# Buckv5.net
KiCad netlist of a schematic drawn in Altium Designer
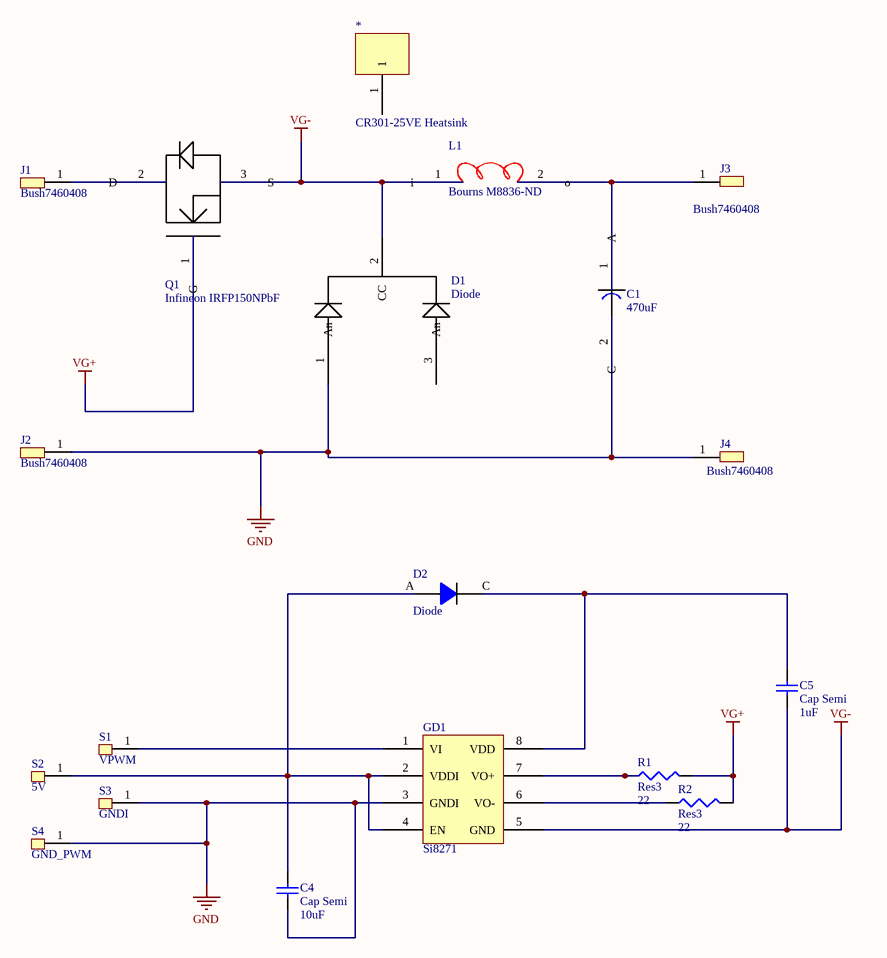
[diagram p0: Buckv5.SchDoc]

(export (version "E")
  (design (tool "Eeschema 10.0.6"))
  (components
    (comp (ref "*")
      (value "CR301-25VE Heatsink")
      (footprint "CR301-25VE")
      (description "Ohmite Heatsink   CR301-25VE Mouser 588-CR301-25VE")
      (libsource (lib "Buck_Library") (part "CR301-25VE Heatsink"))
    )
    (comp (ref "C1")
      (value "470uF")
      (footprint "EPCOS TDK B4851")
      (libsource (lib "Buck_Library") (part "470uF"))
    )
    (comp (ref "C4")
      (value "Cap Semi")
      (footprint "C1210")
      (description "CAP CER 10UF 50V X7S 1210 @Digikey 445-4537-1-ND or C3225X7S1H106M250AB")
      (fields (field (name "ALTIUM_VALUE") "10uF") (field (name "PUBLISHER") "Altium Limited"))
      (libsource (lib "Miscellaneous Devices") (part "Cap Semi"))
    )
    (comp (ref "C5")
      (value "Cap Semi")
      (footprint "C1210")
      (description "Samsung Electro-Mechanics CAP Ceramic 1uF 50V Digikey 1276-1811-1-ND")
      (fields (field (name "ALTIUM_VALUE") "1uF") (field (name "PUBLISHER") "Altium Limited"))
      (libsource (lib "Miscellaneous Devices") (part "Cap Semi"))
    )
    (comp (ref "D1")
      (value "Diode")
      (footprint "TO-247AC")
      (description "Vishay Semiconductors Schottky Rectifier Diode\r\nDigikey VS-STPS30L60CW-N3GI-ND")
      (libsource (lib "Buck_Library") (part "Vishay Semiconductors VS-STPS30L60CW-N3"))
    )
    (comp (ref "D2")
      (value "Diode")
      (footprint "SOD128Diode")
      (description "Schottky Diode 30V 5A\r\nDigikey 568-6519-1-ND")
      (libsource (lib "Buck_Library") (part "Diode"))
    )
    (comp (ref "GD1")
      (value "Si8271")
      (footprint "IPC-7351 SOIC127P600X173-8N")
      (description "8-Pin Gate Driver")
      (libsource (lib "Buck_Library") (part "Si8271"))
    )
    (comp (ref "J1")
      (value "Bush7460408")
      (footprint "Bush7460408")
      (libsource (lib "") (part "Bush7460408_1"))
    )
    (comp (ref "J2")
      (value "Bush7460408")
      (footprint "Bush7460408")
      (libsource (lib "") (part "Bush7460408_1"))
    )
    (comp (ref "J3")
      (value "Bush7460408")
      (footprint "Bush7460408")
      (libsource (lib "Buck_Library") (part "Bush7460408"))
    )
    (comp (ref "J4")
      (value "Bush7460408")
      (footprint "Bush7460408")
      (libsource (lib "Buck_Library") (part "Bush7460408"))
    )
    (comp (ref "L1")
      (value "Bourns M8836-ND")
      (footprint "Bourns M8836-ND")
      (libsource (lib "Buck_Library") (part "Bourns M8836-ND"))
    )
    (comp (ref "Q1")
      (value "Infineon IRFP150NPbF")
      (footprint "Infineon IRFP150NPbF")
      (libsource (lib "Buck_Library") (part "Infineon IRFP150NPbF"))
    )
    (comp (ref "R1")
      (value "Res3")
      (footprint "14-1210")
      (description "Stackpole Electronics Resistor 22 Ohms\r\n0.5W Digikey RMCF1210JT22R0TR-ND")
      (fields (field (name "ALTIUM_VALUE") "22") (field (name "PUBLISHER") "Altium Limited"))
      (libsource (lib "Miscellaneous Devices") (part "Res3"))
    )
    (comp (ref "R2")
      (value "Res3")
      (footprint "14-1210")
      (description "Stackpole Electronics Resistor 22 Ohms\r\n0.5W Digikey RMCF1210JT22R0TR-ND")
      (fields (field (name "ALTIUM_VALUE") "22") (field (name "PUBLISHER") "Altium Limited"))
      (libsource (lib "Miscellaneous Devices") (part "Res3"))
    )
    (comp (ref "S1")
      (value "VPWM")
      (footprint "Sensor_Connecter")
      (description "Sensor Connecter")
      (libsource (lib "Buck_Library") (part "Sensor_Connecter"))
    )
    (comp (ref "S2")
      (value "5V")
      (footprint "Sensor_Connecter")
      (description "Sensor Connecter")
      (libsource (lib "Buck_Library") (part "Sensor_Connecter"))
    )
    (comp (ref "S3")
      (value "GNDI")
      (footprint "Sensor_Connecter")
      (description "Sensor Connecter")
      (libsource (lib "Buck_Library") (part "Sensor_Connecter"))
    )
    (comp (ref "S4")
      (value "GND_PWM")
      (footprint "Sensor_Connecter")
      (description "Sensor Connecter")
      (libsource (lib "Buck_Library") (part "Sensor_Connecter"))
    )
  )
  (nets
    (net (code "1") (name "GND") (class "Default")
      (node (ref "C1") (pin "2") (pinfunction "C_2") (pintype "passive"))
      (node (ref "C4") (pin "1") (pinfunction "1_1") (pintype "passive"))
      (node (ref "D1") (pin "1") (pinfunction "An_1") (pintype "passive"))
      (node (ref "GD1") (pin "3") (pinfunction "GNDI_3") (pintype "passive"))
      (node (ref "J2") (pin "1") (pinfunction "1_1") (pintype "passive"))
      (node (ref "J4") (pin "1") (pinfunction "1_1") (pintype "passive"))
      (node (ref "S3") (pin "1") (pinfunction "1_1") (pintype "passive"))
      (node (ref "S4") (pin "1") (pinfunction "1_1") (pintype "passive"))
    )
    (net (code "2") (name "Net-(C1-A)") (class "Default")
      (node (ref "C1") (pin "1") (pinfunction "A_1") (pintype "passive"))
      (node (ref "J3") (pin "1") (pinfunction "1_1") (pintype "passive"))
      (node (ref "L1") (pin "2") (pinfunction "o_2") (pintype "passive"))
    )
    (net (code "3") (name "Net-(GD1-EN)") (class "Default")
      (node (ref "C4") (pin "2") (pinfunction "2_2") (pintype "passive"))
      (node (ref "D2") (pin "A") (pinfunction "A_A") (pintype "passive"))
      (node (ref "GD1") (pin "2") (pinfunction "VDDI_2") (pintype "passive"))
      (node (ref "GD1") (pin "4") (pinfunction "EN_4") (pintype "passive"))
      (node (ref "S2") (pin "1") (pinfunction "1_1") (pintype "passive"))
    )
    (net (code "4") (name "Net-(GD1-VDD)") (class "Default")
      (node (ref "C5") (pin "2") (pinfunction "2_2") (pintype "passive"))
      (node (ref "D2") (pin "C") (pinfunction "C_C") (pintype "passive"))
      (node (ref "GD1") (pin "8") (pinfunction "VDD_8") (pintype "passive"))
    )
    (net (code "5") (name "Net-(GD1-VI)") (class "Default")
      (node (ref "GD1") (pin "1") (pinfunction "VI_1") (pintype "passive"))
      (node (ref "S1") (pin "1") (pinfunction "1_1") (pintype "passive"))
    )
    (net (code "6") (name "Net-(GD1-VO+)") (class "Default")
      (node (ref "GD1") (pin "7") (pinfunction "VO+_7") (pintype "passive"))
      (node (ref "R1") (pin "1") (pinfunction "1_1") (pintype "passive"))
    )
    (net (code "7") (name "Net-(GD1-VO-)") (class "Default")
      (node (ref "GD1") (pin "6") (pinfunction "VO-_6") (pintype "passive"))
      (node (ref "R2") (pin "1") (pinfunction "1_1") (pintype "passive"))
    )
    (net (code "8") (name "Net-(Q1-D)") (class "Default")
      (node (ref "J1") (pin "1") (pinfunction "1_1") (pintype "passive"))
      (node (ref "Q1") (pin "2") (pinfunction "D_2") (pintype "passive"))
    )
    (net (code "9") (name "VG+") (class "Default")
      (node (ref "Q1") (pin "1") (pinfunction "G_1") (pintype "passive"))
      (node (ref "R1") (pin "2") (pinfunction "2_2") (pintype "passive"))
      (node (ref "R2") (pin "2") (pinfunction "2_2") (pintype "passive"))
    )
    (net (code "10") (name "VG-") (class "Default")
      (node (ref "C5") (pin "1") (pinfunction "1_1") (pintype "passive"))
      (node (ref "D1") (pin "2") (pinfunction "CC_2") (pintype "passive"))
      (node (ref "GD1") (pin "5") (pinfunction "GND_5") (pintype "passive"))
      (node (ref "L1") (pin "1") (pinfunction "i_1") (pintype "passive"))
      (node (ref "Q1") (pin "3") (pinfunction "S_3") (pintype "passive"))
    )
    (net (code "11") (name "unconnected-(*-Pad1)") (class "Default")
      (node (ref "*") (pin "1") (pinfunction "1_1") (pintype "passive"))
    )
    (net (code "12") (name "unconnected-(D1-An-Pad3)") (class "Default")
      (node (ref "D1") (pin "3") (pinfunction "An_3") (pintype "passive"))
    )
  )
)
